# PCB-JOY-4AXIS.net
KiCad netlist of a schematic drawn in EAGLE
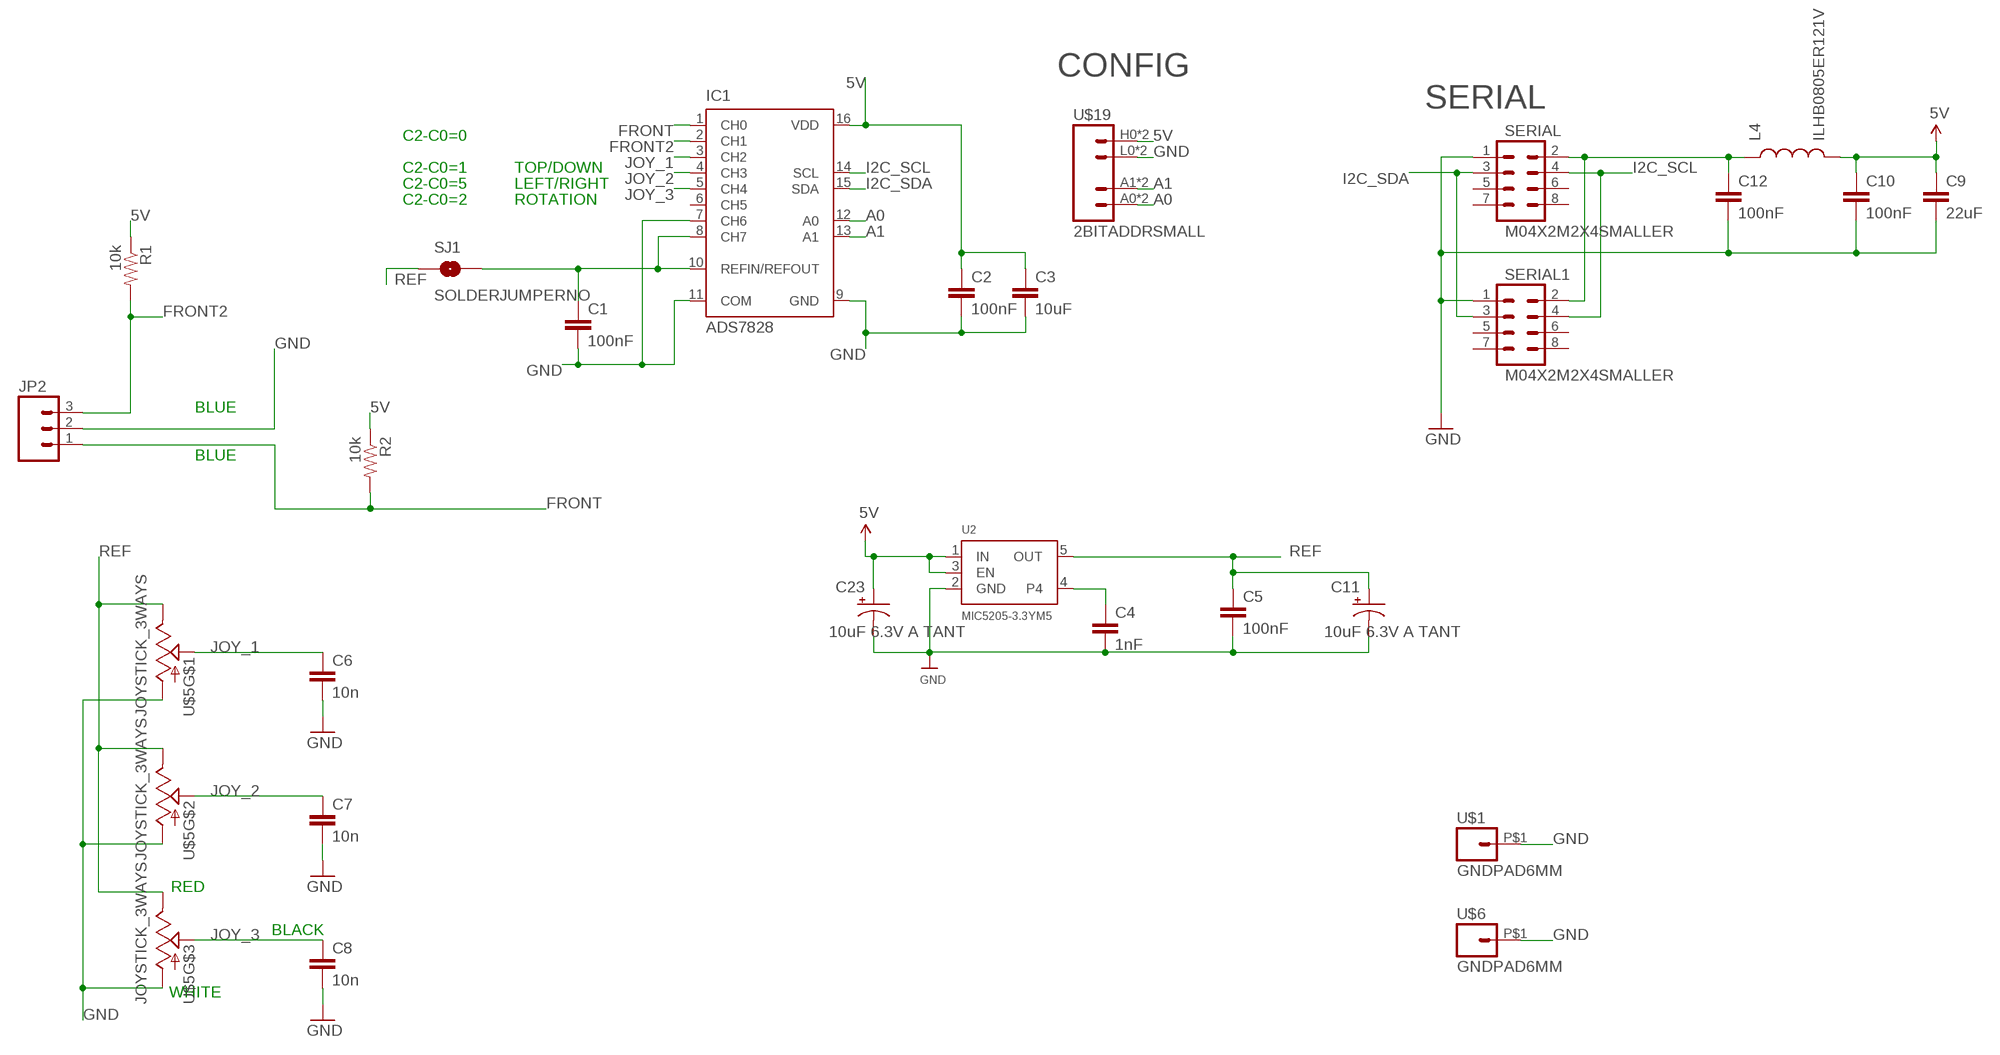
[diagram p0: schematic, sheet 1]

(export (version "E")
  (design (tool "Eeschema 10.0.6"))
  (components
    (comp (ref "C1")
      (value "100nF")
      (footprint "eagle-import:0603-CAP")
      (libsource (lib "eagle-import") (part "CAP0603-CAP"))
    )
    (comp (ref "C2")
      (value "100nF")
      (footprint "eagle-import:0603-CAP")
      (libsource (lib "eagle-import") (part "CAP0603-CAP"))
    )
    (comp (ref "C3")
      (value "10uF")
      (footprint "eagle-import:0805")
      (libsource (lib "eagle-import") (part "CAP0805"))
    )
    (comp (ref "C4")
      (value "1nF")
      (footprint "eagle-import:0603-CAP")
      (libsource (lib "eagle-import") (part "CAP0603-CAP"))
    )
    (comp (ref "C5")
      (value "100nF")
      (footprint "eagle-import:0603-CAP")
      (libsource (lib "eagle-import") (part "CAP0603-CAP"))
    )
    (comp (ref "C6")
      (value "10n")
      (footprint "eagle-import:0603-CAP")
      (libsource (lib "eagle-import") (part "CAP0603-CAP"))
    )
    (comp (ref "C7")
      (value "10n")
      (footprint "eagle-import:0603-CAP")
      (libsource (lib "eagle-import") (part "CAP0603-CAP"))
    )
    (comp (ref "C8")
      (value "10n")
      (footprint "eagle-import:0603-CAP")
      (libsource (lib "eagle-import") (part "CAP0603-CAP"))
    )
    (comp (ref "C9")
      (value "22uF")
      (footprint "eagle-import:0805")
      (libsource (lib "eagle-import") (part "CAP0805"))
    )
    (comp (ref "C10")
      (value "100nF")
      (footprint "eagle-import:0603-CAP")
      (libsource (lib "eagle-import") (part "CAP0603-CAP"))
    )
    (comp (ref "C11")
      (value "10uF 6.3V A TANT")
      (footprint "eagle-import:EIA3216")
      (libsource (lib "eagle-import") (part "CAP_POL1206"))
    )
    (comp (ref "C12")
      (value "100nF")
      (footprint "eagle-import:0603-CAP")
      (libsource (lib "eagle-import") (part "CAP0603-CAP"))
    )
    (comp (ref "C23")
      (value "10uF 6.3V A TANT")
      (footprint "eagle-import:EIA3216")
      (libsource (lib "eagle-import") (part "CAP_POL1206"))
    )
    (comp (ref "IC1")
      (value "ADS7828")
      (footprint "eagle-import:TSSOP16-PW")
      (fields (field (name "MF") "TEXAS INSTRUMENTS") (field (name "MPN") "ADS7828E/250"))
      (libsource (lib "eagle-import") (part "ADS7828"))
    )
    (comp (ref "JP2")
      (value "M03PTH")
      (footprint "eagle-import:1X03")
      (libsource (lib "eagle-import") (part "M03PTH"))
    )
    (comp (ref "L4")
      (value "ILHB0805ER121V")
      (footprint "eagle-import:0805")
      (libsource (lib "eagle-import") (part "INDUCTOR0805"))
    )
    (comp (ref "R1")
      (value "10k")
      (footprint "eagle-import:0603-RES")
      (libsource (lib "eagle-import") (part "RESISTOR0603-RES"))
    )
    (comp (ref "R2")
      (value "10k")
      (footprint "eagle-import:0603-RES")
      (libsource (lib "eagle-import") (part "RESISTOR0603-RES"))
    )
    (comp (ref "SERIAL")
      (value "M04X2M2X4SMALLER")
      (footprint "eagle-import:M2X4SMALLER")
      (libsource (lib "eagle-import") (part "M04X2M2X4SMALLER"))
    )
    (comp (ref "SERIAL1")
      (value "M04X2M2X4SMALLER")
      (footprint "eagle-import:M2X4SMALLER")
      (libsource (lib "eagle-import") (part "M04X2M2X4SMALLER"))
    )
    (comp (ref "SJ1")
      (value "SOLDERJUMPERNO")
      (footprint "eagle-import:SJ_2S-NO")
      (libsource (lib "eagle-import") (part "SOLDERJUMPERNO"))
    )
    (comp (ref "U$1")
      (value "GNDPAD6MM")
      (footprint "eagle-import:3.2MMPAD6MM")
      (libsource (lib "eagle-import") (part "GNDPAD6MM"))
    )
    (comp (ref "U$5")
      (value "JOYSTICK_3WAYS")
      (footprint "eagle-import:JOYSTICK")
      (libsource (lib "eagle-import") (part "JOYSTICK_3WAYS"))
    )
    (comp (ref "U$6")
      (value "GNDPAD6MM")
      (footprint "eagle-import:3.2MMPAD6MM")
      (libsource (lib "eagle-import") (part "GNDPAD6MM"))
    )
    (comp (ref "U$19")
      (value "2BITADDRSMALL")
      (footprint "eagle-import:2BITADDR_SMALL")
      (libsource (lib "eagle-import") (part "2BITADDRSMALL"))
    )
    (comp (ref "U2")
      (value "MIC5205-3.3YM5")
      (footprint "eagle-import:SOT23-5")
      (libsource (lib "eagle-import") (part "VREG_SOT23-5"))
    )
  )
  (nets
    (net (code "1") (name "/A0") (class "Default")
      (node (ref "IC1") (pin "12") (pinfunction "A0_12") (pintype "input"))
      (node (ref "U$19") (pin "A0") (pinfunction "A1_A0") (pintype "passive"))
      (node (ref "U$19") (pin "AS0") (pinfunction "A1_AS0") (pintype "passive"))
    )
    (net (code "2") (name "/A1") (class "Default")
      (node (ref "IC1") (pin "13") (pinfunction "A1_13") (pintype "input"))
      (node (ref "U$19") (pin "A1") (pinfunction "A2_A1") (pintype "passive"))
      (node (ref "U$19") (pin "AS1") (pinfunction "A2_AS1") (pintype "passive"))
    )
    (net (code "3") (name "/FRONT") (class "Default")
      (node (ref "IC1") (pin "1") (pinfunction "CH0_1") (pintype "input"))
      (node (ref "JP2") (pin "1") (pinfunction "1_1") (pintype "passive"))
      (node (ref "R2") (pin "2") (pinfunction "2_2") (pintype "passive"))
    )
    (net (code "4") (name "/FRONT2") (class "Default")
      (node (ref "IC1") (pin "2") (pinfunction "CH1_2") (pintype "input"))
      (node (ref "JP2") (pin "3") (pinfunction "3_3") (pintype "passive"))
      (node (ref "R1") (pin "2") (pinfunction "2_2") (pintype "passive"))
    )
    (net (code "5") (name "/I2C_SCL") (class "Default")
      (node (ref "IC1") (pin "14") (pinfunction "SCL_14") (pintype "input"))
      (node (ref "SERIAL") (pin "4") (pinfunction "4_4") (pintype "passive"))
      (node (ref "SERIAL1") (pin "4") (pinfunction "4_4") (pintype "passive"))
    )
    (net (code "6") (name "/I2C_SDA") (class "Default")
      (node (ref "IC1") (pin "15") (pinfunction "SDA_15") (pintype "bidirectional"))
      (node (ref "SERIAL") (pin "3") (pinfunction "3_3") (pintype "passive"))
      (node (ref "SERIAL1") (pin "3") (pinfunction "3_3") (pintype "passive"))
    )
    (net (code "7") (name "/JOY_1") (class "Default")
      (node (ref "C6") (pin "1") (pinfunction "1_1") (pintype "passive"))
      (node (ref "IC1") (pin "3") (pinfunction "CH2_3") (pintype "input"))
      (node (ref "U$5") (pin "LR_C") (pinfunction "S_LR_C") (pintype "passive"))
    )
    (net (code "8") (name "/JOY_2") (class "Default")
      (node (ref "C7") (pin "1") (pinfunction "1_1") (pintype "passive"))
      (node (ref "IC1") (pin "4") (pinfunction "CH3_4") (pintype "input"))
      (node (ref "U$5") (pin "UD_C") (pinfunction "S_UD_C") (pintype "passive"))
    )
    (net (code "9") (name "/JOY_3") (class "Default")
      (node (ref "C8") (pin "1") (pinfunction "1_1") (pintype "passive"))
      (node (ref "IC1") (pin "5") (pinfunction "CH4_5") (pintype "input"))
      (node (ref "U$5") (pin "ROT_C") (pinfunction "S_ROT_C") (pintype "passive"))
    )
    (net (code "10") (name "/REF") (class "Default")
      (node (ref "C11") (pin "A") (pinfunction "+_A") (pintype "passive"))
      (node (ref "C5") (pin "1") (pinfunction "1_1") (pintype "passive"))
      (node (ref "SJ1") (pin "1") (pinfunction "1_1") (pintype "passive"))
      (node (ref "U$5") (pin "LR_V") (pinfunction "E_LR_V") (pintype "passive"))
      (node (ref "U$5") (pin "ROT_V") (pinfunction "E_ROT_V") (pintype "passive"))
      (node (ref "U$5") (pin "UD_V") (pinfunction "E_UD_V") (pintype "passive"))
      (node (ref "U2") (pin "5") (pinfunction "OUT_5") (pintype "bidirectional"))
    )
    (net (code "11") (name "5V") (class "Default")
      (node (ref "C10") (pin "1") (pinfunction "1_1") (pintype "passive"))
      (node (ref "C2") (pin "1") (pinfunction "1_1") (pintype "passive"))
      (node (ref "C23") (pin "A") (pinfunction "+_A") (pintype "passive"))
      (node (ref "C3") (pin "1") (pinfunction "1_1") (pintype "passive"))
      (node (ref "C9") (pin "1") (pinfunction "1_1") (pintype "passive"))
      (node (ref "IC1") (pin "16") (pinfunction "VDD_16") (pintype "power_in"))
      (node (ref "L4") (pin "2") (pinfunction "2_2") (pintype "passive"))
      (node (ref "R1") (pin "1") (pinfunction "1_1") (pintype "passive"))
      (node (ref "R2") (pin "1") (pinfunction "1_1") (pintype "passive"))
      (node (ref "U$19") (pin "H0") (pinfunction "VCC_H0") (pintype "passive"))
      (node (ref "U$19") (pin "H1") (pinfunction "VCC_H1") (pintype "passive"))
      (node (ref "U2") (pin "1") (pinfunction "IN_1") (pintype "bidirectional"))
      (node (ref "U2") (pin "3") (pinfunction "EN_3") (pintype "bidirectional"))
    )
    (net (code "12") (name "GND") (class "Default")
      (node (ref "C1") (pin "2") (pinfunction "2_2") (pintype "passive"))
      (node (ref "C10") (pin "2") (pinfunction "2_2") (pintype "passive"))
      (node (ref "C11") (pin "C") (pinfunction "-_C") (pintype "passive"))
      (node (ref "C12") (pin "2") (pinfunction "2_2") (pintype "passive"))
      (node (ref "C2") (pin "2") (pinfunction "2_2") (pintype "passive"))
      (node (ref "C23") (pin "C") (pinfunction "-_C") (pintype "passive"))
      (node (ref "C3") (pin "2") (pinfunction "2_2") (pintype "passive"))
      (node (ref "C4") (pin "2") (pinfunction "2_2") (pintype "passive"))
      (node (ref "C5") (pin "2") (pinfunction "2_2") (pintype "passive"))
      (node (ref "C6") (pin "2") (pinfunction "2_2") (pintype "passive"))
      (node (ref "C7") (pin "2") (pinfunction "2_2") (pintype "passive"))
      (node (ref "C8") (pin "2") (pinfunction "2_2") (pintype "passive"))
      (node (ref "C9") (pin "2") (pinfunction "2_2") (pintype "passive"))
      (node (ref "IC1") (pin "11") (pinfunction "COM_11") (pintype "input"))
      (node (ref "IC1") (pin "7") (pinfunction "CH6_7") (pintype "input"))
      (node (ref "IC1") (pin "9") (pinfunction "GND_9") (pintype "power_in"))
      (node (ref "JP2") (pin "2") (pinfunction "2_2") (pintype "passive"))
      (node (ref "SERIAL") (pin "1") (pinfunction "1_1") (pintype "passive"))
      (node (ref "SERIAL1") (pin "1") (pinfunction "1_1") (pintype "passive"))
      (node (ref "U$1") (pin "P$1") (pinfunction "1_P$1") (pintype "passive"))
      (node (ref "U$19") (pin "L0") (pinfunction "GND_L0") (pintype "passive"))
      (node (ref "U$19") (pin "L1") (pinfunction "GND_L1") (pintype "passive"))
      (node (ref "U$5") (pin "LR_COM") (pinfunction "A_LR_COM") (pintype "passive"))
      (node (ref "U$5") (pin "ROT_COM") (pinfunction "A_ROT_COM") (pintype "passive"))
      (node (ref "U$5") (pin "UD_COM") (pinfunction "A_UD_COM") (pintype "passive"))
      (node (ref "U$6") (pin "P$1") (pinfunction "1_P$1") (pintype "passive"))
      (node (ref "U2") (pin "2") (pinfunction "GND_2") (pintype "bidirectional"))
    )
    (net (code "13") (name "Net-(C12-Pad1)") (class "Default")
      (node (ref "C12") (pin "1") (pinfunction "1_1") (pintype "passive"))
      (node (ref "L4") (pin "1") (pinfunction "1_1") (pintype "passive"))
      (node (ref "SERIAL") (pin "2") (pinfunction "2_2") (pintype "passive"))
      (node (ref "SERIAL1") (pin "2") (pinfunction "2_2") (pintype "passive"))
    )
    (net (code "14") (name "Net-(IC1-CH7)") (class "Default")
      (node (ref "C1") (pin "1") (pinfunction "1_1") (pintype "passive"))
      (node (ref "IC1") (pin "10") (pinfunction "REFIN/REFOUT_10") (pintype "passive"))
      (node (ref "IC1") (pin "8") (pinfunction "CH7_8") (pintype "input"))
      (node (ref "SJ1") (pin "2") (pinfunction "2_2") (pintype "passive"))
    )
    (net (code "15") (name "Net-(U2-P4)") (class "Default")
      (node (ref "C4") (pin "1") (pinfunction "1_1") (pintype "passive"))
      (node (ref "U2") (pin "4") (pinfunction "P4_4") (pintype "bidirectional"))
    )
    (net (code "16") (name "unconnected-(IC1-CH5-Pad6)") (class "Default")
      (node (ref "IC1") (pin "6") (pinfunction "CH5_6") (pintype "input"))
    )
    (net (code "17") (name "unconnected-(SERIAL-Pad5)") (class "Default")
      (node (ref "SERIAL") (pin "5") (pinfunction "5_5") (pintype "passive"))
    )
    (net (code "18") (name "unconnected-(SERIAL-Pad6)") (class "Default")
      (node (ref "SERIAL") (pin "6") (pinfunction "6_6") (pintype "passive"))
    )
    (net (code "19") (name "unconnected-(SERIAL-Pad7)") (class "Default")
      (node (ref "SERIAL") (pin "7") (pinfunction "7_7") (pintype "passive"))
    )
    (net (code "20") (name "unconnected-(SERIAL-Pad8)") (class "Default")
      (node (ref "SERIAL") (pin "8") (pinfunction "8_8") (pintype "passive"))
    )
    (net (code "21") (name "unconnected-(SERIAL1-Pad5)") (class "Default")
      (node (ref "SERIAL1") (pin "5") (pinfunction "5_5") (pintype "passive"))
    )
    (net (code "22") (name "unconnected-(SERIAL1-Pad6)") (class "Default")
      (node (ref "SERIAL1") (pin "6") (pinfunction "6_6") (pintype "passive"))
    )
    (net (code "23") (name "unconnected-(SERIAL1-Pad7)") (class "Default")
      (node (ref "SERIAL1") (pin "7") (pinfunction "7_7") (pintype "passive"))
    )
    (net (code "24") (name "unconnected-(SERIAL1-Pad8)") (class "Default")
      (node (ref "SERIAL1") (pin "8") (pinfunction "8_8") (pintype "passive"))
    )
  )
)
